# Digital_Input_LED_Monitor.net
KiCad netlist of a schematic drawn in Altium Designer
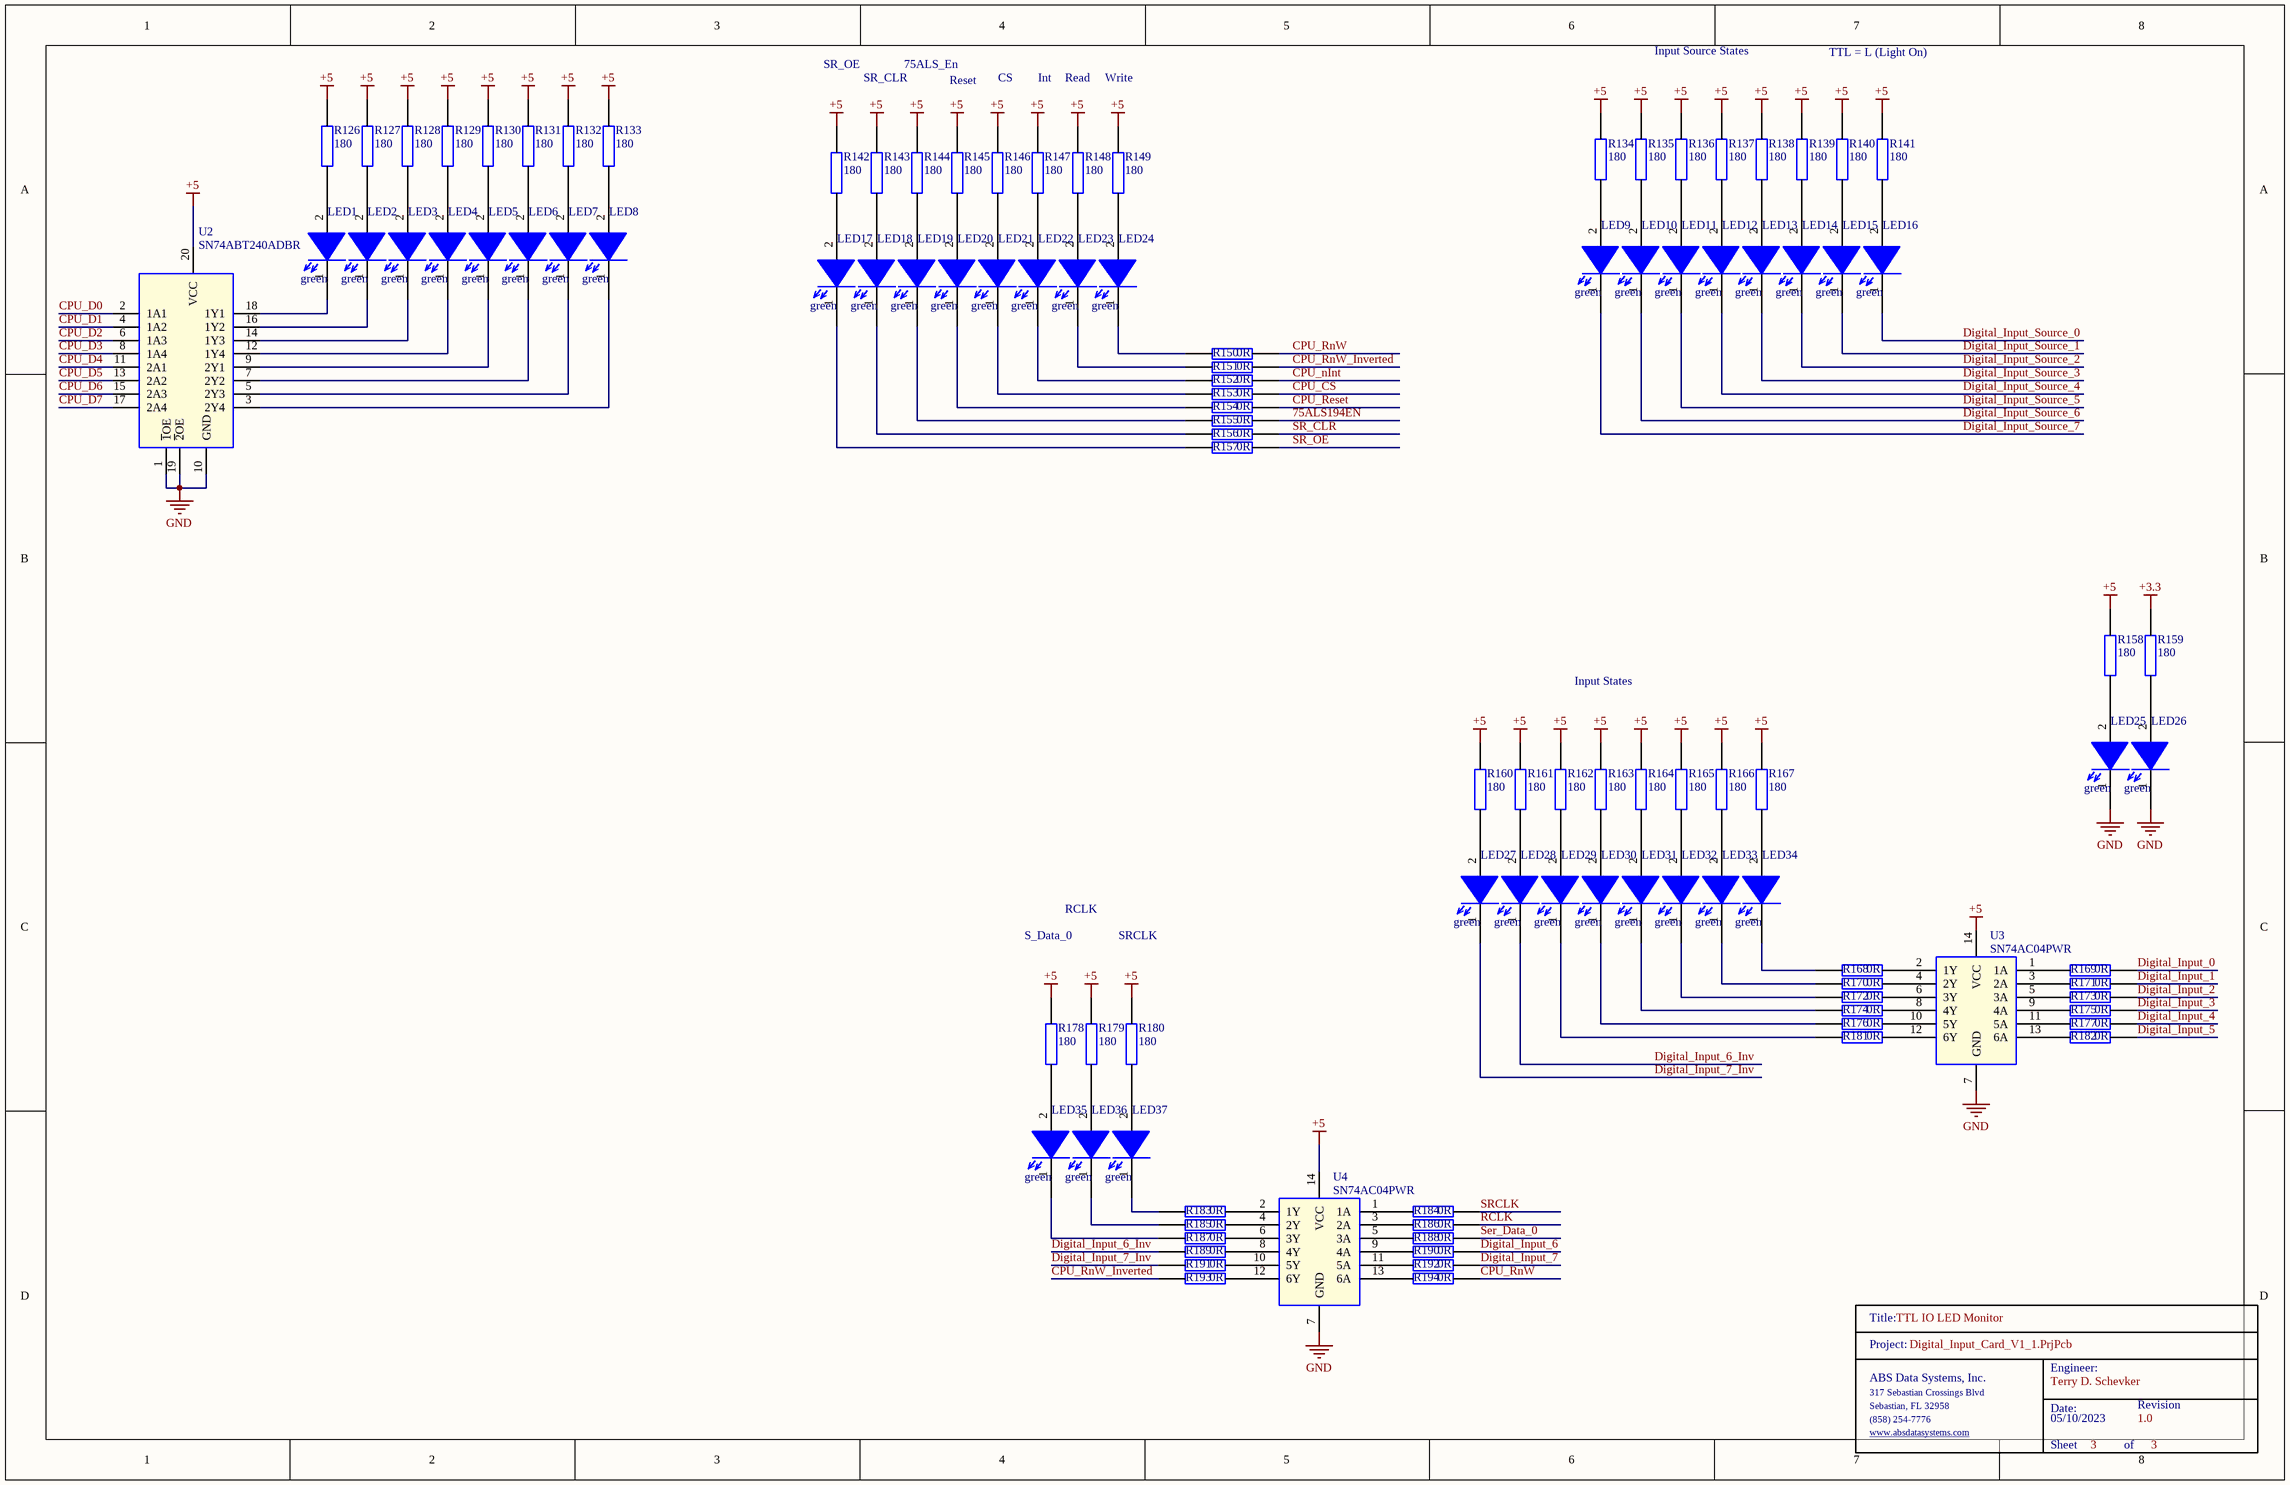
[diagram p0: Digital_Input_LED_Monitor.SchDoc]

(export (version "E")
  (design (tool "Eeschema 10.0.6"))
  (components
    (comp (ref "LED1")
      (value "green")
      (footprint "0603_Diode")
      (description "Wurth Elektronik 0603 green")
      (fields
        (field (name "MANUFACTURER") "Wurth Electronics")
        (field (name "MANUFACTURER PART NUMBER") "150060GS75000")
      )
      (libsource (lib "Misc") (part "150060GS75000"))
    )
    (comp (ref "LED2")
      (value "green")
      (footprint "0603_Diode")
      (description "Wurth Elektronik 0603 green")
      (fields
        (field (name "MANUFACTURER") "Wurth Electronics")
        (field (name "MANUFACTURER PART NUMBER") "150060GS75000")
      )
      (libsource (lib "Misc") (part "150060GS75000"))
    )
    (comp (ref "LED3")
      (value "green")
      (footprint "0603_Diode")
      (description "Wurth Elektronik 0603 green")
      (fields
        (field (name "MANUFACTURER") "Wurth Electronics")
        (field (name "MANUFACTURER PART NUMBER") "150060GS75000")
      )
      (libsource (lib "Misc") (part "150060GS75000"))
    )
    (comp (ref "LED4")
      (value "green")
      (footprint "0603_Diode")
      (description "Wurth Elektronik 0603 green")
      (fields
        (field (name "MANUFACTURER") "Wurth Electronics")
        (field (name "MANUFACTURER PART NUMBER") "150060GS75000")
      )
      (libsource (lib "Misc") (part "150060GS75000"))
    )
    (comp (ref "LED5")
      (value "green")
      (footprint "0603_Diode")
      (description "Wurth Elektronik 0603 green")
      (fields
        (field (name "MANUFACTURER") "Wurth Electronics")
        (field (name "MANUFACTURER PART NUMBER") "150060GS75000")
      )
      (libsource (lib "Misc") (part "150060GS75000"))
    )
    (comp (ref "LED6")
      (value "green")
      (footprint "0603_Diode")
      (description "Wurth Elektronik 0603 green")
      (fields
        (field (name "MANUFACTURER") "Wurth Electronics")
        (field (name "MANUFACTURER PART NUMBER") "150060GS75000")
      )
      (libsource (lib "Misc") (part "150060GS75000"))
    )
    (comp (ref "LED7")
      (value "green")
      (footprint "0603_Diode")
      (description "Wurth Elektronik 0603 green")
      (fields
        (field (name "MANUFACTURER") "Wurth Electronics")
        (field (name "MANUFACTURER PART NUMBER") "150060GS75000")
      )
      (libsource (lib "Misc") (part "150060GS75000"))
    )
    (comp (ref "LED8")
      (value "green")
      (footprint "0603_Diode")
      (description "Wurth Elektronik 0603 green")
      (fields
        (field (name "MANUFACTURER") "Wurth Electronics")
        (field (name "MANUFACTURER PART NUMBER") "150060GS75000")
      )
      (libsource (lib "Misc") (part "150060GS75000"))
    )
    (comp (ref "LED9")
      (value "green")
      (footprint "0603_Diode")
      (description "Wurth Elektronik 0603 green")
      (fields
        (field (name "MANUFACTURER") "Wurth Electronics")
        (field (name "MANUFACTURER PART NUMBER") "150060GS75000")
      )
      (libsource (lib "Misc") (part "150060GS75000"))
    )
    (comp (ref "LED10")
      (value "green")
      (footprint "0603_Diode")
      (description "Wurth Elektronik 0603 green")
      (fields
        (field (name "MANUFACTURER") "Wurth Electronics")
        (field (name "MANUFACTURER PART NUMBER") "150060GS75000")
      )
      (libsource (lib "Misc") (part "150060GS75000"))
    )
    (comp (ref "LED11")
      (value "green")
      (footprint "0603_Diode")
      (description "Wurth Elektronik 0603 green")
      (fields
        (field (name "MANUFACTURER") "Wurth Electronics")
        (field (name "MANUFACTURER PART NUMBER") "150060GS75000")
      )
      (libsource (lib "Misc") (part "150060GS75000"))
    )
    (comp (ref "LED12")
      (value "green")
      (footprint "0603_Diode")
      (description "Wurth Elektronik 0603 green")
      (fields
        (field (name "MANUFACTURER") "Wurth Electronics")
        (field (name "MANUFACTURER PART NUMBER") "150060GS75000")
      )
      (libsource (lib "Misc") (part "150060GS75000"))
    )
    (comp (ref "LED13")
      (value "green")
      (footprint "0603_Diode")
      (description "Wurth Elektronik 0603 green")
      (fields
        (field (name "MANUFACTURER") "Wurth Electronics")
        (field (name "MANUFACTURER PART NUMBER") "150060GS75000")
      )
      (libsource (lib "Misc") (part "150060GS75000"))
    )
    (comp (ref "LED14")
      (value "green")
      (footprint "0603_Diode")
      (description "Wurth Elektronik 0603 green")
      (fields
        (field (name "MANUFACTURER") "Wurth Electronics")
        (field (name "MANUFACTURER PART NUMBER") "150060GS75000")
      )
      (libsource (lib "Misc") (part "150060GS75000"))
    )
    (comp (ref "LED15")
      (value "green")
      (footprint "0603_Diode")
      (description "Wurth Elektronik 0603 green")
      (fields
        (field (name "MANUFACTURER") "Wurth Electronics")
        (field (name "MANUFACTURER PART NUMBER") "150060GS75000")
      )
      (libsource (lib "Misc") (part "150060GS75000"))
    )
    (comp (ref "LED16")
      (value "green")
      (footprint "0603_Diode")
      (description "Wurth Elektronik 0603 green")
      (fields
        (field (name "MANUFACTURER") "Wurth Electronics")
        (field (name "MANUFACTURER PART NUMBER") "150060GS75000")
      )
      (libsource (lib "Misc") (part "150060GS75000"))
    )
    (comp (ref "LED17")
      (value "green")
      (footprint "0603_Diode")
      (description "Wurth Elektronik 0603 green")
      (fields
        (field (name "MANUFACTURER") "Wurth Electronics")
        (field (name "MANUFACTURER PART NUMBER") "150060GS75000")
      )
      (libsource (lib "Misc") (part "150060GS75000"))
    )
    (comp (ref "LED18")
      (value "green")
      (footprint "0603_Diode")
      (description "Wurth Elektronik 0603 green")
      (fields
        (field (name "MANUFACTURER") "Wurth Electronics")
        (field (name "MANUFACTURER PART NUMBER") "150060GS75000")
      )
      (libsource (lib "Misc") (part "150060GS75000"))
    )
    (comp (ref "LED19")
      (value "green")
      (footprint "0603_Diode")
      (description "Wurth Elektronik 0603 green")
      (fields
        (field (name "MANUFACTURER") "Wurth Electronics")
        (field (name "MANUFACTURER PART NUMBER") "150060GS75000")
      )
      (libsource (lib "Misc") (part "150060GS75000"))
    )
    (comp (ref "LED20")
      (value "green")
      (footprint "0603_Diode")
      (description "Wurth Elektronik 0603 green")
      (fields
        (field (name "MANUFACTURER") "Wurth Electronics")
        (field (name "MANUFACTURER PART NUMBER") "150060GS75000")
      )
      (libsource (lib "Misc") (part "150060GS75000"))
    )
    (comp (ref "LED21")
      (value "green")
      (footprint "0603_Diode")
      (description "Wurth Elektronik 0603 green")
      (fields
        (field (name "MANUFACTURER") "Wurth Electronics")
        (field (name "MANUFACTURER PART NUMBER") "150060GS75000")
      )
      (libsource (lib "Misc") (part "150060GS75000"))
    )
    (comp (ref "LED22")
      (value "green")
      (footprint "0603_Diode")
      (description "Wurth Elektronik 0603 green")
      (fields
        (field (name "MANUFACTURER") "Wurth Electronics")
        (field (name "MANUFACTURER PART NUMBER") "150060GS75000")
      )
      (libsource (lib "Misc") (part "150060GS75000"))
    )
    (comp (ref "LED23")
      (value "green")
      (footprint "0603_Diode")
      (description "Wurth Elektronik 0603 green")
      (fields
        (field (name "MANUFACTURER") "Wurth Electronics")
        (field (name "MANUFACTURER PART NUMBER") "150060GS75000")
      )
      (libsource (lib "Misc") (part "150060GS75000"))
    )
    (comp (ref "LED24")
      (value "green")
      (footprint "0603_Diode")
      (description "Wurth Elektronik 0603 green")
      (fields
        (field (name "MANUFACTURER") "Wurth Electronics")
        (field (name "MANUFACTURER PART NUMBER") "150060GS75000")
      )
      (libsource (lib "Misc") (part "150060GS75000"))
    )
    (comp (ref "LED25")
      (value "green")
      (footprint "0603_Diode")
      (description "Wurth Elektronik 0603 green")
      (fields
        (field (name "MANUFACTURER") "Wurth Electronics")
        (field (name "MANUFACTURER PART NUMBER") "150060GS75000")
      )
      (libsource (lib "Misc") (part "150060GS75000"))
    )
    (comp (ref "LED26")
      (value "green")
      (footprint "0603_Diode")
      (description "Wurth Elektronik 0603 green")
      (fields
        (field (name "MANUFACTURER") "Wurth Electronics")
        (field (name "MANUFACTURER PART NUMBER") "150060GS75000")
      )
      (libsource (lib "Misc") (part "150060GS75000"))
    )
    (comp (ref "LED27")
      (value "green")
      (footprint "0603_Diode")
      (description "Wurth Elektronik 0603 green")
      (fields
        (field (name "MANUFACTURER") "Wurth Electronics")
        (field (name "MANUFACTURER PART NUMBER") "150060GS75000")
      )
      (libsource (lib "Misc") (part "150060GS75000"))
    )
    (comp (ref "LED28")
      (value "green")
      (footprint "0603_Diode")
      (description "Wurth Elektronik 0603 green")
      (fields
        (field (name "MANUFACTURER") "Wurth Electronics")
        (field (name "MANUFACTURER PART NUMBER") "150060GS75000")
      )
      (libsource (lib "Misc") (part "150060GS75000"))
    )
    (comp (ref "LED29")
      (value "green")
      (footprint "0603_Diode")
      (description "Wurth Elektronik 0603 green")
      (fields
        (field (name "MANUFACTURER") "Wurth Electronics")
        (field (name "MANUFACTURER PART NUMBER") "150060GS75000")
      )
      (libsource (lib "Misc") (part "150060GS75000"))
    )
    (comp (ref "LED30")
      (value "green")
      (footprint "0603_Diode")
      (description "Wurth Elektronik 0603 green")
      (fields
        (field (name "MANUFACTURER") "Wurth Electronics")
        (field (name "MANUFACTURER PART NUMBER") "150060GS75000")
      )
      (libsource (lib "Misc") (part "150060GS75000"))
    )
    (comp (ref "LED31")
      (value "green")
      (footprint "0603_Diode")
      (description "Wurth Elektronik 0603 green")
      (fields
        (field (name "MANUFACTURER") "Wurth Electronics")
        (field (name "MANUFACTURER PART NUMBER") "150060GS75000")
      )
      (libsource (lib "Misc") (part "150060GS75000"))
    )
    (comp (ref "LED32")
      (value "green")
      (footprint "0603_Diode")
      (description "Wurth Elektronik 0603 green")
      (fields
        (field (name "MANUFACTURER") "Wurth Electronics")
        (field (name "MANUFACTURER PART NUMBER") "150060GS75000")
      )
      (libsource (lib "Misc") (part "150060GS75000"))
    )
    (comp (ref "LED33")
      (value "green")
      (footprint "0603_Diode")
      (description "Wurth Elektronik 0603 green")
      (fields
        (field (name "MANUFACTURER") "Wurth Electronics")
        (field (name "MANUFACTURER PART NUMBER") "150060GS75000")
      )
      (libsource (lib "Misc") (part "150060GS75000"))
    )
    (comp (ref "LED34")
      (value "green")
      (footprint "0603_Diode")
      (description "Wurth Elektronik 0603 green")
      (fields
        (field (name "MANUFACTURER") "Wurth Electronics")
        (field (name "MANUFACTURER PART NUMBER") "150060GS75000")
      )
      (libsource (lib "Misc") (part "150060GS75000"))
    )
    (comp (ref "LED35")
      (value "green")
      (footprint "0603_Diode")
      (description "Wurth Elektronik 0603 green")
      (fields
        (field (name "MANUFACTURER") "Wurth Electronics")
        (field (name "MANUFACTURER PART NUMBER") "150060GS75000")
      )
      (libsource (lib "Misc") (part "150060GS75000"))
    )
    (comp (ref "LED36")
      (value "green")
      (footprint "0603_Diode")
      (description "Wurth Elektronik 0603 green")
      (fields
        (field (name "MANUFACTURER") "Wurth Electronics")
        (field (name "MANUFACTURER PART NUMBER") "150060GS75000")
      )
      (libsource (lib "Misc") (part "150060GS75000"))
    )
    (comp (ref "LED37")
      (value "green")
      (footprint "0603_Diode")
      (description "Wurth Elektronik 0603 green")
      (fields
        (field (name "MANUFACTURER") "Wurth Electronics")
        (field (name "MANUFACTURER PART NUMBER") "150060GS75000")
      )
      (libsource (lib "Misc") (part "150060GS75000"))
    )
    (comp (ref "R126")
      (value "180")
      (footprint "0603")
      (description "YAGEO 0603 180 ohm")
      (fields
        (field (name "MOUSER PART NUMBER") "603-RC0603JR-070RL")
        (field (name "MANUFACTURER_PART_NUMBER") "RC0603JR-070RL")
      )
      (libsource (lib "Resistors") (part "RC0603FR-13180RL"))
    )
    (comp (ref "R127")
      (value "180")
      (footprint "0603")
      (description "YAGEO 0603 180 ohm")
      (fields
        (field (name "MOUSER PART NUMBER") "603-RC0603JR-070RL")
        (field (name "MANUFACTURER_PART_NUMBER") "RC0603JR-070RL")
      )
      (libsource (lib "Resistors") (part "RC0603FR-13180RL"))
    )
    (comp (ref "R128")
      (value "180")
      (footprint "0603")
      (description "YAGEO 0603 180 ohm")
      (fields
        (field (name "MOUSER PART NUMBER") "603-RC0603JR-070RL")
        (field (name "MANUFACTURER_PART_NUMBER") "RC0603JR-070RL")
      )
      (libsource (lib "Resistors") (part "RC0603FR-13180RL"))
    )
    (comp (ref "R129")
      (value "180")
      (footprint "0603")
      (description "YAGEO 0603 180 ohm")
      (fields
        (field (name "MOUSER PART NUMBER") "603-RC0603JR-070RL")
        (field (name "MANUFACTURER_PART_NUMBER") "RC0603JR-070RL")
      )
      (libsource (lib "Resistors") (part "RC0603FR-13180RL"))
    )
    (comp (ref "R130")
      (value "180")
      (footprint "0603")
      (description "YAGEO 0603 180 ohm")
      (fields
        (field (name "MOUSER PART NUMBER") "603-RC0603JR-070RL")
        (field (name "MANUFACTURER_PART_NUMBER") "RC0603JR-070RL")
      )
      (libsource (lib "Resistors") (part "RC0603FR-13180RL"))
    )
    (comp (ref "R131")
      (value "180")
      (footprint "0603")
      (description "YAGEO 0603 180 ohm")
      (fields
        (field (name "MOUSER PART NUMBER") "603-RC0603JR-070RL")
        (field (name "MANUFACTURER_PART_NUMBER") "RC0603JR-070RL")
      )
      (libsource (lib "Resistors") (part "RC0603FR-13180RL"))
    )
    (comp (ref "R132")
      (value "180")
      (footprint "0603")
      (description "YAGEO 0603 180 ohm")
      (fields
        (field (name "MOUSER PART NUMBER") "603-RC0603JR-070RL")
        (field (name "MANUFACTURER_PART_NUMBER") "RC0603JR-070RL")
      )
      (libsource (lib "Resistors") (part "RC0603FR-13180RL"))
    )
    (comp (ref "R133")
      (value "180")
      (footprint "0603")
      (description "YAGEO 0603 180 ohm")
      (fields
        (field (name "MOUSER PART NUMBER") "603-RC0603JR-070RL")
        (field (name "MANUFACTURER_PART_NUMBER") "RC0603JR-070RL")
      )
      (libsource (lib "Resistors") (part "RC0603FR-13180RL"))
    )
    (comp (ref "R134")
      (value "180")
      (footprint "0603")
      (description "YAGEO 0603 180 ohm")
      (fields
        (field (name "MOUSER PART NUMBER") "603-RC0603JR-070RL")
        (field (name "MANUFACTURER_PART_NUMBER") "RC0603JR-070RL")
      )
      (libsource (lib "Resistors") (part "RC0603FR-13180RL"))
    )
    (comp (ref "R135")
      (value "180")
      (footprint "0603")
      (description "YAGEO 0603 180 ohm")
      (fields
        (field (name "MOUSER PART NUMBER") "603-RC0603JR-070RL")
        (field (name "MANUFACTURER_PART_NUMBER") "RC0603JR-070RL")
      )
      (libsource (lib "Resistors") (part "RC0603FR-13180RL"))
    )
    (comp (ref "R136")
      (value "180")
      (footprint "0603")
      (description "YAGEO 0603 180 ohm")
      (fields
        (field (name "MOUSER PART NUMBER") "603-RC0603JR-070RL")
        (field (name "MANUFACTURER_PART_NUMBER") "RC0603JR-070RL")
      )
      (libsource (lib "Resistors") (part "RC0603FR-13180RL"))
    )
    (comp (ref "R137")
      (value "180")
      (footprint "0603")
      (description "YAGEO 0603 180 ohm")
      (fields
        (field (name "MOUSER PART NUMBER") "603-RC0603JR-070RL")
        (field (name "MANUFACTURER_PART_NUMBER") "RC0603JR-070RL")
      )
      (libsource (lib "Resistors") (part "RC0603FR-13180RL"))
    )
    (comp (ref "R138")
      (value "180")
      (footprint "0603")
      (description "YAGEO 0603 180 ohm")
      (fields
        (field (name "MOUSER PART NUMBER") "603-RC0603JR-070RL")
        (field (name "MANUFACTURER_PART_NUMBER") "RC0603JR-070RL")
      )
      (libsource (lib "Resistors") (part "RC0603FR-13180RL"))
    )
    (comp (ref "R139")
      (value "180")
      (footprint "0603")
      (description "YAGEO 0603 180 ohm")
      (fields
        (field (name "MOUSER PART NUMBER") "603-RC0603JR-070RL")
        (field (name "MANUFACTURER_PART_NUMBER") "RC0603JR-070RL")
      )
      (libsource (lib "Resistors") (part "RC0603FR-13180RL"))
    )
    (comp (ref "R140")
      (value "180")
      (footprint "0603")
      (description "YAGEO 0603 180 ohm")
      (fields
        (field (name "MOUSER PART NUMBER") "603-RC0603JR-070RL")
        (field (name "MANUFACTURER_PART_NUMBER") "RC0603JR-070RL")
      )
      (libsource (lib "Resistors") (part "RC0603FR-13180RL"))
    )
    (comp (ref "R141")
      (value "180")
      (footprint "0603")
      (description "YAGEO 0603 180 ohm")
      (fields
        (field (name "MOUSER PART NUMBER") "603-RC0603JR-070RL")
        (field (name "MANUFACTURER_PART_NUMBER") "RC0603JR-070RL")
      )
      (libsource (lib "Resistors") (part "RC0603FR-13180RL"))
    )
    (comp (ref "R142")
      (value "180")
      (footprint "0603")
      (description "YAGEO 0603 180 ohm")
      (fields
        (field (name "MOUSER PART NUMBER") "603-RC0603JR-070RL")
        (field (name "MANUFACTURER_PART_NUMBER") "RC0603JR-070RL")
      )
      (libsource (lib "Resistors") (part "RC0603FR-13180RL"))
    )
    (comp (ref "R143")
      (value "180")
      (footprint "0603")
      (description "YAGEO 0603 180 ohm")
      (fields
        (field (name "MOUSER PART NUMBER") "603-RC0603JR-070RL")
        (field (name "MANUFACTURER_PART_NUMBER") "RC0603JR-070RL")
      )
      (libsource (lib "Resistors") (part "RC0603FR-13180RL"))
    )
    (comp (ref "R144")
      (value "180")
      (footprint "0603")
      (description "YAGEO 0603 180 ohm")
      (fields
        (field (name "MOUSER PART NUMBER") "603-RC0603JR-070RL")
        (field (name "MANUFACTURER_PART_NUMBER") "RC0603JR-070RL")
      )
      (libsource (lib "Resistors") (part "RC0603FR-13180RL"))
    )
    (comp (ref "R145")
      (value "180")
      (footprint "0603")
      (description "YAGEO 0603 180 ohm")
      (fields
        (field (name "MOUSER PART NUMBER") "603-RC0603JR-070RL")
        (field (name "MANUFACTURER_PART_NUMBER") "RC0603JR-070RL")
      )
      (libsource (lib "Resistors") (part "RC0603FR-13180RL"))
    )
    (comp (ref "R146")
      (value "180")
      (footprint "0603")
      (description "YAGEO 0603 180 ohm")
      (fields
        (field (name "MOUSER PART NUMBER") "603-RC0603JR-070RL")
        (field (name "MANUFACTURER_PART_NUMBER") "RC0603JR-070RL")
      )
      (libsource (lib "Resistors") (part "RC0603FR-13180RL"))
    )
    (comp (ref "R147")
      (value "180")
      (footprint "0603")
      (description "YAGEO 0603 180 ohm")
      (fields
        (field (name "MOUSER PART NUMBER") "603-RC0603JR-070RL")
        (field (name "MANUFACTURER_PART_NUMBER") "RC0603JR-070RL")
      )
      (libsource (lib "Resistors") (part "RC0603FR-13180RL"))
    )
    (comp (ref "R148")
      (value "180")
      (footprint "0603")
      (description "YAGEO 0603 180 ohm")
      (fields
        (field (name "MOUSER PART NUMBER") "603-RC0603JR-070RL")
        (field (name "MANUFACTURER_PART_NUMBER") "RC0603JR-070RL")
      )
      (libsource (lib "Resistors") (part "RC0603FR-13180RL"))
    )
    (comp (ref "R149")
      (value "180")
      (footprint "0603")
      (description "YAGEO 0603 180 ohm")
      (fields
        (field (name "MOUSER PART NUMBER") "603-RC0603JR-070RL")
        (field (name "MANUFACTURER_PART_NUMBER") "RC0603JR-070RL")
      )
      (libsource (lib "Resistors") (part "RC0603FR-13180RL"))
    )
    (comp (ref "R150")
      (value "0R")
      (footprint "0603")
      (description "YAGEO 0603 0 ohm")
      (fields
        (field (name "MOUSER PART NUMBER") "603-RC0603JR-070RL")
        (field (name "MANUFACTURER_PART_NUMBER") "RC0603JR-070RL")
      )
      (libsource (lib "Resistors") (part "RC0603JR-070RL"))
    )
    (comp (ref "R151")
      (value "0R")
      (footprint "0603")
      (description "YAGEO 0603 0 ohm")
      (fields
        (field (name "MOUSER PART NUMBER") "603-RC0603JR-070RL")
        (field (name "MANUFACTURER_PART_NUMBER") "RC0603JR-070RL")
      )
      (libsource (lib "Resistors") (part "RC0603JR-070RL"))
    )
    (comp (ref "R152")
      (value "0R")
      (footprint "0603")
      (description "YAGEO 0603 0 ohm")
      (fields
        (field (name "MOUSER PART NUMBER") "603-RC0603JR-070RL")
        (field (name "MANUFACTURER_PART_NUMBER") "RC0603JR-070RL")
      )
      (libsource (lib "Resistors") (part "RC0603JR-070RL"))
    )
    (comp (ref "R153")
      (value "0R")
      (footprint "0603")
      (description "YAGEO 0603 0 ohm")
      (fields
        (field (name "MOUSER PART NUMBER") "603-RC0603JR-070RL")
        (field (name "MANUFACTURER_PART_NUMBER") "RC0603JR-070RL")
      )
      (libsource (lib "Resistors") (part "RC0603JR-070RL"))
    )
    (comp (ref "R154")
      (value "0R")
      (footprint "0603")
      (description "YAGEO 0603 0 ohm")
      (fields
        (field (name "MOUSER PART NUMBER") "603-RC0603JR-070RL")
        (field (name "MANUFACTURER_PART_NUMBER") "RC0603JR-070RL")
      )
      (libsource (lib "Resistors") (part "RC0603JR-070RL"))
    )
    (comp (ref "R155")
      (value "0R")
      (footprint "0603")
      (description "YAGEO 0603 0 ohm")
      (fields
        (field (name "MOUSER PART NUMBER") "603-RC0603JR-070RL")
        (field (name "MANUFACTURER_PART_NUMBER") "RC0603JR-070RL")
      )
      (libsource (lib "Resistors") (part "RC0603JR-070RL"))
    )
    (comp (ref "R156")
      (value "0R")
      (footprint "0603")
      (description "YAGEO 0603 0 ohm")
      (fields
        (field (name "MOUSER PART NUMBER") "603-RC0603JR-070RL")
        (field (name "MANUFACTURER_PART_NUMBER") "RC0603JR-070RL")
      )
      (libsource (lib "Resistors") (part "RC0603JR-070RL"))
    )
    (comp (ref "R157")
      (value "0R")
      (footprint "0603")
      (description "YAGEO 0603 0 ohm")
      (fields
        (field (name "MOUSER PART NUMBER") "603-RC0603JR-070RL")
        (field (name "MANUFACTURER_PART_NUMBER") "RC0603JR-070RL")
      )
      (libsource (lib "Resistors") (part "RC0603JR-070RL"))
    )
    (comp (ref "R158")
      (value "180")
      (footprint "0603")
      (description "YAGEO 0603 180 ohm")
      (fields
        (field (name "MOUSER PART NUMBER") "603-RC0603JR-070RL")
        (field (name "MANUFACTURER_PART_NUMBER") "RC0603JR-070RL")
      )
      (libsource (lib "Resistors") (part "RC0603FR-13180RL"))
    )
    (comp (ref "R159")
      (value "180")
      (footprint "0603")
      (description "YAGEO 0603 180 ohm")
      (fields
        (field (name "MOUSER PART NUMBER") "603-RC0603JR-070RL")
        (field (name "MANUFACTURER_PART_NUMBER") "RC0603JR-070RL")
      )
      (libsource (lib "Resistors") (part "RC0603FR-13180RL"))
    )
    (comp (ref "R160")
      (value "180")
      (footprint "0603")
      (description "YAGEO 0603 180 ohm")
      (fields
        (field (name "MOUSER PART NUMBER") "603-RC0603JR-070RL")
        (field (name "MANUFACTURER_PART_NUMBER") "RC0603JR-070RL")
      )
      (libsource (lib "Resistors") (part "RC0603FR-13180RL"))
    )
    (comp (ref "R161")
      (value "180")
      (footprint "0603")
      (description "YAGEO 0603 180 ohm")
      (fields
        (field (name "MOUSER PART NUMBER") "603-RC0603JR-070RL")
        (field (name "MANUFACTURER_PART_NUMBER") "RC0603JR-070RL")
      )
      (libsource (lib "Resistors") (part "RC0603FR-13180RL"))
    )
    (comp (ref "R162")
      (value "180")
      (footprint "0603")
      (description "YAGEO 0603 180 ohm")
      (fields
        (field (name "MOUSER PART NUMBER") "603-RC0603JR-070RL")
        (field (name "MANUFACTURER_PART_NUMBER") "RC0603JR-070RL")
      )
      (libsource (lib "Resistors") (part "RC0603FR-13180RL"))
    )
    (comp (ref "R163")
      (value "180")
      (footprint "0603")
      (description "YAGEO 0603 180 ohm")
      (fields
        (field (name "MOUSER PART NUMBER") "603-RC0603JR-070RL")
        (field (name "MANUFACTURER_PART_NUMBER") "RC0603JR-070RL")
      )
      (libsource (lib "Resistors") (part "RC0603FR-13180RL"))
    )
    (comp (ref "R164")
      (value "180")
      (footprint "0603")
      (description "YAGEO 0603 180 ohm")
      (fields
        (field (name "MOUSER PART NUMBER") "603-RC0603JR-070RL")
        (field (name "MANUFACTURER_PART_NUMBER") "RC0603JR-070RL")
      )
      (libsource (lib "Resistors") (part "RC0603FR-13180RL"))
    )
    (comp (ref "R165")
      (value "180")
      (footprint "0603")
      (description "YAGEO 0603 180 ohm")
      (fields
        (field (name "MOUSER PART NUMBER") "603-RC0603JR-070RL")
        (field (name "MANUFACTURER_PART_NUMBER") "RC0603JR-070RL")
      )
      (libsource (lib "Resistors") (part "RC0603FR-13180RL"))
    )
    (comp (ref "R166")
      (value "180")
      (footprint "0603")
      (description "YAGEO 0603 180 ohm")
      (fields
        (field (name "MOUSER PART NUMBER") "603-RC0603JR-070RL")
        (field (name "MANUFACTURER_PART_NUMBER") "RC0603JR-070RL")
      )
      (libsource (lib "Resistors") (part "RC0603FR-13180RL"))
    )
    (comp (ref "R167")
      (value "180")
      (footprint "0603")
      (description "YAGEO 0603 180 ohm")
      (fields
        (field (name "MOUSER PART NUMBER") "603-RC0603JR-070RL")
        (field (name "MANUFACTURER_PART_NUMBER") "RC0603JR-070RL")
      )
      (libsource (lib "Resistors") (part "RC0603FR-13180RL"))
    )
    (comp (ref "R168")
      (value "0R")
      (footprint "0603")
      (description "YAGEO 0603 0 ohm")
      (fields
        (field (name "MOUSER PART NUMBER") "603-RC0603JR-070RL")
        (field (name "MANUFACTURER_PART_NUMBER") "RC0603JR-070RL")
      )
      (libsource (lib "Resistors") (part "RC0603JR-070RL"))
    )
    (comp (ref "R169")
      (value "0R")
      (footprint "0603")
      (description "YAGEO 0603 0 ohm")
      (fields
        (field (name "MOUSER PART NUMBER") "603-RC0603JR-070RL")
        (field (name "MANUFACTURER_PART_NUMBER") "RC0603JR-070RL")
      )
      (libsource (lib "Resistors") (part "RC0603JR-070RL"))
    )
    (comp (ref "R170")
      (value "0R")
      (footprint "0603")
      (description "YAGEO 0603 0 ohm")
      (fields
        (field (name "MOUSER PART NUMBER") "603-RC0603JR-070RL")
        (field (name "MANUFACTURER_PART_NUMBER") "RC0603JR-070RL")
      )
      (libsource (lib "Resistors") (part "RC0603JR-070RL"))
    )
    (comp (ref "R171")
      (value "0R")
      (footprint "0603")
      (description "YAGEO 0603 0 ohm")
      (fields
        (field (name "MOUSER PART NUMBER") "603-RC0603JR-070RL")
        (field (name "MANUFACTURER_PART_NUMBER") "RC0603JR-070RL")
      )
      (libsource (lib "Resistors") (part "RC0603JR-070RL"))
    )
    (comp (ref "R172")
      (value "0R")
      (footprint "0603")
      (description "YAGEO 0603 0 ohm")
      (fields
        (field (name "MOUSER PART NUMBER") "603-RC0603JR-070RL")
        (field (name "MANUFACTURER_PART_NUMBER") "RC0603JR-070RL")
      )
      (libsource (lib "Resistors") (part "RC0603JR-070RL"))
    )
    (comp (ref "R173")
      (value "0R")
      (footprint "0603")
      (description "YAGEO 0603 0 ohm")
      (fields
        (field (name "MOUSER PART NUMBER") "603-RC0603JR-070RL")
        (field (name "MANUFACTURER_PART_NUMBER") "RC0603JR-070RL")
      )
      (libsource (lib "Resistors") (part "RC0603JR-070RL"))
    )
    (comp (ref "R174")
      (value "0R")
      (footprint "0603")
      (description "YAGEO 0603 0 ohm")
      (fields
        (field (name "MOUSER PART NUMBER") "603-RC0603JR-070RL")
        (field (name "MANUFACTURER_PART_NUMBER") "RC0603JR-070RL")
      )
      (libsource (lib "Resistors") (part "RC0603JR-070RL"))
    )
    (comp (ref "R175")
      (value "0R")
      (footprint "0603")
      (description "YAGEO 0603 0 ohm")
      (fields
        (field (name "MOUSER PART NUMBER") "603-RC0603JR-070RL")
        (field (name "MANUFACTURER_PART_NUMBER") "RC0603JR-070RL")
      )
      (libsource (lib "Resistors") (part "RC0603JR-070RL"))
    )
    (comp (ref "R176")
      (value "0R")
      (footprint "0603")
      (description "YAGEO 0603 0 ohm")
      (fields
        (field (name "MOUSER PART NUMBER") "603-RC0603JR-070RL")
        (field (name "MANUFACTURER_PART_NUMBER") "RC0603JR-070RL")
      )
      (libsource (lib "Resistors") (part "RC0603JR-070RL"))
    )
    (comp (ref "R177")
      (value "0R")
      (footprint "0603")
      (description "YAGEO 0603 0 ohm")
      (fields
        (field (name "MOUSER PART NUMBER") "603-RC0603JR-070RL")
        (field (name "MANUFACTURER_PART_NUMBER") "RC0603JR-070RL")
      )
      (libsource (lib "Resistors") (part "RC0603JR-070RL"))
    )
    (comp (ref "R178")
      (value "180")
      (footprint "0603")
      (description "YAGEO 0603 180 ohm")
      (fields
        (field (name "MOUSER PART NUMBER") "603-RC0603JR-070RL")
        (field (name "MANUFACTURER_PART_NUMBER") "RC0603JR-070RL")
      )
      (libsource (lib "Resistors") (part "RC0603FR-13180RL"))
    )
    (comp (ref "R179")
      (value "180")
      (footprint "0603")
      (description "YAGEO 0603 180 ohm")
      (fields
        (field (name "MOUSER PART NUMBER") "603-RC0603JR-070RL")
        (field (name "MANUFACTURER_PART_NUMBER") "RC0603JR-070RL")
      )
      (libsource (lib "Resistors") (part "RC0603FR-13180RL"))
    )
    (comp (ref "R180")
      (value "180")
      (footprint "0603")
      (description "YAGEO 0603 180 ohm")
      (fields
        (field (name "MOUSER PART NUMBER") "603-RC0603JR-070RL")
        (field (name "MANUFACTURER_PART_NUMBER") "RC0603JR-070RL")
      )
      (libsource (lib "Resistors") (part "RC0603FR-13180RL"))
    )
    (comp (ref "R181")
      (value "0R")
      (footprint "0603")
      (description "YAGEO 0603 0 ohm")
      (fields
        (field (name "MOUSER PART NUMBER") "603-RC0603JR-070RL")
        (field (name "MANUFACTURER_PART_NUMBER") "RC0603JR-070RL")
      )
      (libsource (lib "Resistors") (part "RC0603JR-070RL"))
    )
    (comp (ref "R182")
      (value "0R")
      (footprint "0603")
      (description "YAGEO 0603 0 ohm")
      (fields
        (field (name "MOUSER PART NUMBER") "603-RC0603JR-070RL")
        (field (name "MANUFACTURER_PART_NUMBER") "RC0603JR-070RL")
      )
      (libsource (lib "Resistors") (part "RC0603JR-070RL"))
    )
    (comp (ref "R183")
      (value "0R")
      (footprint "0603")
      (description "YAGEO 0603 0 ohm")
      (fields
        (field (name "MOUSER PART NUMBER") "603-RC0603JR-070RL")
        (field (name "MANUFACTURER_PART_NUMBER") "RC0603JR-070RL")
      )
      (libsource (lib "Resistors") (part "RC0603JR-070RL"))
    )
    (comp (ref "R184")
      (value "0R")
      (footprint "0603")
      (description "YAGEO 0603 0 ohm")
      (fields
        (field (name "MOUSER PART NUMBER") "603-RC0603JR-070RL")
        (field (name "MANUFACTURER_PART_NUMBER") "RC0603JR-070RL")
      )
      (libsource (lib "Resistors") (part "RC0603JR-070RL"))
    )
    (comp (ref "R185")
      (value "0R")
      (footprint "0603")
      (description "YAGEO 0603 0 ohm")
      (fields
        (field (name "MOUSER PART NUMBER") "603-RC0603JR-070RL")
        (field (name "MANUFACTURER_PART_NUMBER") "RC0603JR-070RL")
      )
      (libsource (lib "Resistors") (part "RC0603JR-070RL"))
    )
    (comp (ref "R186")
      (value "0R")
      (footprint "0603")
      (description "YAGEO 0603 0 ohm")
      (fields
        (field (name "MOUSER PART NUMBER") "603-RC0603JR-070RL")
        (field (name "MANUFACTURER_PART_NUMBER") "RC0603JR-070RL")
      )
      (libsource (lib "Resistors") (part "RC0603JR-070RL"))
    )
    (comp (ref "R187")
      (value "0R")
      (footprint "0603")
      (description "YAGEO 0603 0 ohm")
      (fields
        (field (name "MOUSER PART NUMBER") "603-RC0603JR-070RL")
        (field (name "MANUFACTURER_PART_NUMBER") "RC0603JR-070RL")
      )
      (libsource (lib "Resistors") (part "RC0603JR-070RL"))
    )
    (comp (ref "R188")
      (value "0R")
      (footprint "0603")
      (description "YAGEO 0603 0 ohm")
      (fields
        (field (name "MOUSER PART NUMBER") "603-RC0603JR-070RL")
        (field (name "MANUFACTURER_PART_NUMBER") "RC0603JR-070RL")
      )
      (libsource (lib "Resistors") (part "RC0603JR-070RL"))
    )
    (comp (ref "R189")
      (value "0R")
      (footprint "0603")
      (description "YAGEO 0603 0 ohm")
      (fields
        (field (name "MOUSER PART NUMBER") "603-RC0603JR-070RL")
        (field (name "MANUFACTURER_PART_NUMBER") "RC0603JR-070RL")
      )
      (libsource (lib "Resistors") (part "RC0603JR-070RL"))
    )
    (comp (ref "R190")
      (value "0R")
      (footprint "0603")
      (description "YAGEO 0603 0 ohm")
      (fields
        (field (name "MOUSER PART NUMBER") "603-RC0603JR-070RL")
        (field (name "MANUFACTURER_PART_NUMBER") "RC0603JR-070RL")
      )
      (libsource (lib "Resistors") (part "RC0603JR-070RL"))
    )
    (comp (ref "R191")
      (value "0R")
      (footprint "0603")
      (description "YAGEO 0603 0 ohm")
      (fields
        (field (name "MOUSER PART NUMBER") "603-RC0603JR-070RL")
        (field (name "MANUFACTURER_PART_NUMBER") "RC0603JR-070RL")
      )
      (libsource (lib "Resistors") (part "RC0603JR-070RL"))
    )
    (comp (ref "R192")
      (value "0R")
      (footprint "0603")
      (description "YAGEO 0603 0 ohm")
      (fields
        (field (name "MOUSER PART NUMBER") "603-RC0603JR-070RL")
        (field (name "MANUFACTURER_PART_NUMBER") "RC0603JR-070RL")
      )
      (libsource (lib "Resistors") (part "RC0603JR-070RL"))
    )
    (comp (ref "R193")
      (value "0R")
      (footprint "0603")
      (description "YAGEO 0603 0 ohm")
      (fields
        (field (name "MOUSER PART NUMBER") "603-RC0603JR-070RL")
        (field (name "MANUFACTURER_PART_NUMBER") "RC0603JR-070RL")
      )
      (libsource (lib "Resistors") (part "RC0603JR-070RL"))
    )
    (comp (ref "R194")
      (value "0R")
      (footprint "0603")
      (description "YAGEO 0603 0 ohm")
      (fields
        (field (name "MOUSER PART NUMBER") "603-RC0603JR-070RL")
        (field (name "MANUFACTURER_PART_NUMBER") "RC0603JR-070RL")
      )
      (libsource (lib "Resistors") (part "RC0603JR-070RL"))
    )
    (comp (ref "TitleBlock_2") (value "TitleBlock") (libsource (lib "Misc") (part "TitleBlock")))
    (comp (ref "U2")
      (value "SN74ABT240ADBR")
      (footprint "SOP65P780X200-20N")
      (description "Octal Buffers/Drivers With 3-State Outputs")
      (fields (field (name "MOUSER PART NUMBER") "595-SN74ABT240ADBR"))
      (libsource (lib "Logic") (part "SN74ABT240ADBR"))
    )
    (comp (ref "U3")
      (value "SN74AC04PWR")
      (footprint "SOP65P640X120-14N")
      (description "Hex Inverters")
      (fields (field (name "MOUSER PART NUMBER") "595-SN74AC04PWR"))
      (libsource (lib "Logic") (part "SN74AC04PWR"))
    )
    (comp (ref "U4")
      (value "SN74AC04PWR")
      (footprint "SOP65P640X120-14N")
      (description "Hex Inverters")
      (fields (field (name "MOUSER PART NUMBER") "595-SN74AC04PWR"))
      (libsource (lib "Logic") (part "SN74AC04PWR"))
    )
  )
  (nets
    (net (code "1") (name "+3.3") (class "Default")
      (node (ref "R159") (pin "2") (pinfunction "2_2") (pintype "passive"))
    )
    (net (code "2") (name "+5") (class "Default")
      (node (ref "R126") (pin "2") (pinfunction "2_2") (pintype "passive"))
      (node (ref "R127") (pin "2") (pinfunction "2_2") (pintype "passive"))
      (node (ref "R128") (pin "2") (pinfunction "2_2") (pintype "passive"))
      (node (ref "R129") (pin "2") (pinfunction "2_2") (pintype "passive"))
      (node (ref "R130") (pin "2") (pinfunction "2_2") (pintype "passive"))
      (node (ref "R131") (pin "2") (pinfunction "2_2") (pintype "passive"))
      (node (ref "R132") (pin "2") (pinfunction "2_2") (pintype "passive"))
      (node (ref "R133") (pin "2") (pinfunction "2_2") (pintype "passive"))
      (node (ref "R134") (pin "2") (pinfunction "2_2") (pintype "passive"))
      (node (ref "R135") (pin "2") (pinfunction "2_2") (pintype "passive"))
      (node (ref "R136") (pin "2") (pinfunction "2_2") (pintype "passive"))
      (node (ref "R137") (pin "2") (pinfunction "2_2") (pintype "passive"))
      (node (ref "R138") (pin "2") (pinfunction "2_2") (pintype "passive"))
      (node (ref "R139") (pin "2") (pinfunction "2_2") (pintype "passive"))
      (node (ref "R140") (pin "2") (pinfunction "2_2") (pintype "passive"))
      (node (ref "R141") (pin "2") (pinfunction "2_2") (pintype "passive"))
      (node (ref "R142") (pin "2") (pinfunction "2_2") (pintype "passive"))
      (node (ref "R143") (pin "2") (pinfunction "2_2") (pintype "passive"))
      (node (ref "R144") (pin "2") (pinfunction "2_2") (pintype "passive"))
      (node (ref "R145") (pin "2") (pinfunction "2_2") (pintype "passive"))
      (node (ref "R146") (pin "2") (pinfunction "2_2") (pintype "passive"))
      (node (ref "R147") (pin "2") (pinfunction "2_2") (pintype "passive"))
      (node (ref "R148") (pin "2") (pinfunction "2_2") (pintype "passive"))
      (node (ref "R149") (pin "2") (pinfunction "2_2") (pintype "passive"))
      (node (ref "R158") (pin "2") (pinfunction "2_2") (pintype "passive"))
      (node (ref "R160") (pin "2") (pinfunction "2_2") (pintype "passive"))
      (node (ref "R161") (pin "2") (pinfunction "2_2") (pintype "passive"))
      (node (ref "R162") (pin "2") (pinfunction "2_2") (pintype "passive"))
      (node (ref "R163") (pin "2") (pinfunction "2_2") (pintype "passive"))
      (node (ref "R164") (pin "2") (pinfunction "2_2") (pintype "passive"))
      (node (ref "R165") (pin "2") (pinfunction "2_2") (pintype "passive"))
      (node (ref "R166") (pin "2") (pinfunction "2_2") (pintype "passive"))
      (node (ref "R167") (pin "2") (pinfunction "2_2") (pintype "passive"))
      (node (ref "R178") (pin "2") (pinfunction "2_2") (pintype "passive"))
      (node (ref "R179") (pin "2") (pinfunction "2_2") (pintype "passive"))
      (node (ref "R180") (pin "2") (pinfunction "2_2") (pintype "passive"))
      (node (ref "U2") (pin "20") (pinfunction "VCC_20") (pintype "passive"))
      (node (ref "U3") (pin "14") (pinfunction "VCC_14") (pintype "passive"))
      (node (ref "U4") (pin "14") (pinfunction "VCC_14") (pintype "passive"))
    )
    (net (code "3") (name "/75ALS194EN") (class "Default")
      (node (ref "R155") (pin "2") (pinfunction "2_2") (pintype "passive"))
    )
    (net (code "4") (name "/CPU_CS") (class "Default")
      (node (ref "R153") (pin "2") (pinfunction "2_2") (pintype "passive"))
    )
    (net (code "5") (name "/CPU_D0") (class "Default")
      (node (ref "U2") (pin "2") (pinfunction "1A1_2") (pintype "passive"))
    )
    (net (code "6") (name "/CPU_D1") (class "Default")
      (node (ref "U2") (pin "4") (pinfunction "1A2_4") (pintype "passive"))
    )
    (net (code "7") (name "/CPU_D2") (class "Default")
      (node (ref "U2") (pin "6") (pinfunction "1A3_6") (pintype "passive"))
    )
    (net (code "8") (name "/CPU_D3") (class "Default")
      (node (ref "U2") (pin "8") (pinfunction "1A4_8") (pintype "passive"))
    )
    (net (code "9") (name "/CPU_D4") (class "Default")
      (node (ref "U2") (pin "11") (pinfunction "2A1_11") (pintype "passive"))
    )
    (net (code "10") (name "/CPU_D5") (class "Default")
      (node (ref "U2") (pin "13") (pinfunction "2A2_13") (pintype "passive"))
    )
    (net (code "11") (name "/CPU_D6") (class "Default")
      (node (ref "U2") (pin "15") (pinfunction "2A3_15") (pintype "passive"))
    )
    (net (code "12") (name "/CPU_D7") (class "Default")
      (node (ref "U2") (pin "17") (pinfunction "2A4_17") (pintype "passive"))
    )
    (net (code "13") (name "/CPU_Reset") (class "Default")
      (node (ref "R154") (pin "2") (pinfunction "2_2") (pintype "passive"))
    )
    (net (code "14") (name "/CPU_RnW") (class "Default")
      (node (ref "R150") (pin "2") (pinfunction "2_2") (pintype "passive"))
      (node (ref "R194") (pin "2") (pinfunction "2_2") (pintype "passive"))
    )
    (net (code "15") (name "/CPU_RnW_Inverted") (class "Default")
      (node (ref "R151") (pin "2") (pinfunction "2_2") (pintype "passive"))
      (node (ref "R193") (pin "1") (pinfunction "1_1") (pintype "passive"))
    )
    (net (code "16") (name "/CPU_nInt") (class "Default")
      (node (ref "R152") (pin "2") (pinfunction "2_2") (pintype "passive"))
    )
    (net (code "17") (name "/Digital_Input_0") (class "Default")
      (node (ref "R169") (pin "2") (pinfunction "2_2") (pintype "passive"))
    )
    (net (code "18") (name "/Digital_Input_1") (class "Default")
      (node (ref "R171") (pin "2") (pinfunction "2_2") (pintype "passive"))
    )
    (net (code "19") (name "/Digital_Input_2") (class "Default")
      (node (ref "R173") (pin "2") (pinfunction "2_2") (pintype "passive"))
    )
    (net (code "20") (name "/Digital_Input_3") (class "Default")
      (node (ref "R175") (pin "2") (pinfunction "2_2") (pintype "passive"))
    )
    (net (code "21") (name "/Digital_Input_4") (class "Default")
      (node (ref "R177") (pin "2") (pinfunction "2_2") (pintype "passive"))
    )
    (net (code "22") (name "/Digital_Input_5") (class "Default")
      (node (ref "R182") (pin "2") (pinfunction "2_2") (pintype "passive"))
    )
    (net (code "23") (name "/Digital_Input_6") (class "Default")
      (node (ref "R190") (pin "2") (pinfunction "2_2") (pintype "passive"))
    )
    (net (code "24") (name "/Digital_Input_6_Inv") (class "Default")
      (node (ref "LED28") (pin "1") (pinfunction "K_1") (pintype "passive"))
      (node (ref "R189") (pin "1") (pinfunction "1_1") (pintype "passive"))
    )
    (net (code "25") (name "/Digital_Input_7") (class "Default")
      (node (ref "R192") (pin "2") (pinfunction "2_2") (pintype "passive"))
    )
    (net (code "26") (name "/Digital_Input_7_Inv") (class "Default")
      (node (ref "LED27") (pin "1") (pinfunction "K_1") (pintype "passive"))
      (node (ref "R191") (pin "1") (pinfunction "1_1") (pintype "passive"))
    )
    (net (code "27") (name "/Digital_Input_Source_0") (class "Default")
      (node (ref "LED16") (pin "1") (pinfunction "K_1") (pintype "passive"))
    )
    (net (code "28") (name "/Digital_Input_Source_1") (class "Default")
      (node (ref "LED15") (pin "1") (pinfunction "K_1") (pintype "passive"))
    )
    (net (code "29") (name "/Digital_Input_Source_2") (class "Default")
      (node (ref "LED14") (pin "1") (pinfunction "K_1") (pintype "passive"))
    )
    (net (code "30") (name "/Digital_Input_Source_3") (class "Default")
      (node (ref "LED13") (pin "1") (pinfunction "K_1") (pintype "passive"))
    )
    (net (code "31") (name "/Digital_Input_Source_4") (class "Default")
      (node (ref "LED12") (pin "1") (pinfunction "K_1") (pintype "passive"))
    )
    (net (code "32") (name "/Digital_Input_Source_5") (class "Default")
      (node (ref "LED11") (pin "1") (pinfunction "K_1") (pintype "passive"))
    )
    (net (code "33") (name "/Digital_Input_Source_6") (class "Default")
      (node (ref "LED10") (pin "1") (pinfunction "K_1") (pintype "passive"))
    )
    (net (code "34") (name "/Digital_Input_Source_7") (class "Default")
      (node (ref "LED9") (pin "1") (pinfunction "K_1") (pintype "passive"))
    )
    (net (code "35") (name "/RCLK") (class "Default")
      (node (ref "R186") (pin "2") (pinfunction "2_2") (pintype "passive"))
    )
    (net (code "36") (name "/SRCLK") (class "Default")
      (node (ref "R184") (pin "2") (pinfunction "2_2") (pintype "passive"))
    )
    (net (code "37") (name "/SR_CLR") (class "Default")
      (node (ref "R156") (pin "2") (pinfunction "2_2") (pintype "passive"))
    )
    (net (code "38") (name "/SR_OE") (class "Default")
      (node (ref "R157") (pin "2") (pinfunction "2_2") (pintype "passive"))
    )
    (net (code "39") (name "/Ser_Data_0") (class "Default")
      (node (ref "R188") (pin "2") (pinfunction "2_2") (pintype "passive"))
    )
    (net (code "40") (name "GND") (class "Default")
      (node (ref "LED25") (pin "1") (pinfunction "K_1") (pintype "passive"))
      (node (ref "LED26") (pin "1") (pinfunction "K_1") (pintype "passive"))
      (node (ref "U2") (pin "1") (pinfunction "~{1}OE_1") (pintype "passive"))
      (node (ref "U2") (pin "10") (pinfunction "GND_10") (pintype "passive"))
      (node (ref "U2") (pin "19") (pinfunction "~{2}OE_19") (pintype "passive"))
      (node (ref "U3") (pin "7") (pinfunction "GND_7") (pintype "passive"))
      (node (ref "U4") (pin "7") (pinfunction "GND_7") (pintype "passive"))
    )
    (net (code "41") (name "Net-(LED1-A)") (class "Default")
      (node (ref "LED1") (pin "2") (pinfunction "A_2") (pintype "passive"))
      (node (ref "R126") (pin "1") (pinfunction "1_1") (pintype "passive"))
    )
    (net (code "42") (name "Net-(LED1-K)") (class "Default")
      (node (ref "LED1") (pin "1") (pinfunction "K_1") (pintype "passive"))
      (node (ref "U2") (pin "18") (pinfunction "1Y1_18") (pintype "passive"))
    )
    (net (code "43") (name "Net-(LED2-A)") (class "Default")
      (node (ref "LED2") (pin "2") (pinfunction "A_2") (pintype "passive"))
      (node (ref "R127") (pin "1") (pinfunction "1_1") (pintype "passive"))
    )
    (net (code "44") (name "Net-(LED2-K)") (class "Default")
      (node (ref "LED2") (pin "1") (pinfunction "K_1") (pintype "passive"))
      (node (ref "U2") (pin "16") (pinfunction "1Y2_16") (pintype "passive"))
    )
    (net (code "45") (name "Net-(LED3-A)") (class "Default")
      (node (ref "LED3") (pin "2") (pinfunction "A_2") (pintype "passive"))
      (node (ref "R128") (pin "1") (pinfunction "1_1") (pintype "passive"))
    )
    (net (code "46") (name "Net-(LED3-K)") (class "Default")
      (node (ref "LED3") (pin "1") (pinfunction "K_1") (pintype "passive"))
      (node (ref "U2") (pin "14") (pinfunction "1Y3_14") (pintype "passive"))
    )
    (net (code "47") (name "Net-(LED4-A)") (class "Default")
      (node (ref "LED4") (pin "2") (pinfunction "A_2") (pintype "passive"))
      (node (ref "R129") (pin "1") (pinfunction "1_1") (pintype "passive"))
    )
    (net (code "48") (name "Net-(LED4-K)") (class "Default")
      (node (ref "LED4") (pin "1") (pinfunction "K_1") (pintype "passive"))
      (node (ref "U2") (pin "12") (pinfunction "1Y4_12") (pintype "passive"))
    )
    (net (code "49") (name "Net-(LED5-A)") (class "Default")
      (node (ref "LED5") (pin "2") (pinfunction "A_2") (pintype "passive"))
      (node (ref "R130") (pin "1") (pinfunction "1_1") (pintype "passive"))
    )
    (net (code "50") (name "Net-(LED5-K)") (class "Default")
      (node (ref "LED5") (pin "1") (pinfunction "K_1") (pintype "passive"))
      (node (ref "U2") (pin "9") (pinfunction "2Y1_9") (pintype "passive"))
    )
    (net (code "51") (name "Net-(LED6-A)") (class "Default")
      (node (ref "LED6") (pin "2") (pinfunction "A_2") (pintype "passive"))
      (node (ref "R131") (pin "1") (pinfunction "1_1") (pintype "passive"))
    )
    (net (code "52") (name "Net-(LED6-K)") (class "Default")
      (node (ref "LED6") (pin "1") (pinfunction "K_1") (pintype "passive"))
      (node (ref "U2") (pin "7") (pinfunction "2Y2_7") (pintype "passive"))
    )
    (net (code "53") (name "Net-(LED7-A)") (class "Default")
      (node (ref "LED7") (pin "2") (pinfunction "A_2") (pintype "passive"))
      (node (ref "R132") (pin "1") (pinfunction "1_1") (pintype "passive"))
    )
    (net (code "54") (name "Net-(LED7-K)") (class "Default")
      (node (ref "LED7") (pin "1") (pinfunction "K_1") (pintype "passive"))
      (node (ref "U2") (pin "5") (pinfunction "2Y3_5") (pintype "passive"))
    )
    (net (code "55") (name "Net-(LED8-A)") (class "Default")
      (node (ref "LED8") (pin "2") (pinfunction "A_2") (pintype "passive"))
      (node (ref "R133") (pin "1") (pinfunction "1_1") (pintype "passive"))
    )
    (net (code "56") (name "Net-(LED8-K)") (class "Default")
      (node (ref "LED8") (pin "1") (pinfunction "K_1") (pintype "passive"))
      (node (ref "U2") (pin "3") (pinfunction "2Y4_3") (pintype "passive"))
    )
    (net (code "57") (name "Net-(LED9-A)") (class "Default")
      (node (ref "LED9") (pin "2") (pinfunction "A_2") (pintype "passive"))
      (node (ref "R134") (pin "1") (pinfunction "1_1") (pintype "passive"))
    )
    (net (code "58") (name "Net-(LED10-A)") (class "Default")
      (node (ref "LED10") (pin "2") (pinfunction "A_2") (pintype "passive"))
      (node (ref "R135") (pin "1") (pinfunction "1_1") (pintype "passive"))
    )
    (net (code "59") (name "Net-(LED11-A)") (class "Default")
      (node (ref "LED11") (pin "2") (pinfunction "A_2") (pintype "passive"))
      (node (ref "R136") (pin "1") (pinfunction "1_1") (pintype "passive"))
    )
    (net (code "60") (name "Net-(LED12-A)") (class "Default")
      (node (ref "LED12") (pin "2") (pinfunction "A_2") (pintype "passive"))
      (node (ref "R137") (pin "1") (pinfunction "1_1") (pintype "passive"))
    )
    (net (code "61") (name "Net-(LED13-A)") (class "Default")
      (node (ref "LED13") (pin "2") (pinfunction "A_2") (pintype "passive"))
      (node (ref "R138") (pin "1") (pinfunction "1_1") (pintype "passive"))
    )
    (net (code "62") (name "Net-(LED14-A)") (class "Default")
      (node (ref "LED14") (pin "2") (pinfunction "A_2") (pintype "passive"))
      (node (ref "R139") (pin "1") (pinfunction "1_1") (pintype "passive"))
    )
    (net (code "63") (name "Net-(LED15-A)") (class "Default")
      (node (ref "LED15") (pin "2") (pinfunction "A_2") (pintype "passive"))
      (node (ref "R140") (pin "1") (pinfunction "1_1") (pintype "passive"))
    )
    (net (code "64") (name "Net-(LED16-A)") (class "Default")
      (node (ref "LED16") (pin "2") (pinfunction "A_2") (pintype "passive"))
      (node (ref "R141") (pin "1") (pinfunction "1_1") (pintype "passive"))
    )
    (net (code "65") (name "Net-(LED17-A)") (class "Default")
      (node (ref "LED17") (pin "2") (pinfunction "A_2") (pintype "passive"))
      (node (ref "R142") (pin "1") (pinfunction "1_1") (pintype "passive"))
    )
    (net (code "66") (name "Net-(LED17-K)") (class "Default")
      (node (ref "LED17") (pin "1") (pinfunction "K_1") (pintype "passive"))
      (node (ref "R157") (pin "1") (pinfunction "1_1") (pintype "passive"))
    )
    (net (code "67") (name "Net-(LED18-A)") (class "Default")
      (node (ref "LED18") (pin "2") (pinfunction "A_2") (pintype "passive"))
      (node (ref "R143") (pin "1") (pinfunction "1_1") (pintype "passive"))
    )
    (net (code "68") (name "Net-(LED18-K)") (class "Default")
      (node (ref "LED18") (pin "1") (pinfunction "K_1") (pintype "passive"))
      (node (ref "R156") (pin "1") (pinfunction "1_1") (pintype "passive"))
    )
    (net (code "69") (name "Net-(LED19-A)") (class "Default")
      (node (ref "LED19") (pin "2") (pinfunction "A_2") (pintype "passive"))
      (node (ref "R144") (pin "1") (pinfunction "1_1") (pintype "passive"))
    )
    (net (code "70") (name "Net-(LED19-K)") (class "Default")
      (node (ref "LED19") (pin "1") (pinfunction "K_1") (pintype "passive"))
      (node (ref "R155") (pin "1") (pinfunction "1_1") (pintype "passive"))
    )
    (net (code "71") (name "Net-(LED20-A)") (class "Default")
      (node (ref "LED20") (pin "2") (pinfunction "A_2") (pintype "passive"))
      (node (ref "R145") (pin "1") (pinfunction "1_1") (pintype "passive"))
    )
    (net (code "72") (name "Net-(LED20-K)") (class "Default")
      (node (ref "LED20") (pin "1") (pinfunction "K_1") (pintype "passive"))
      (node (ref "R154") (pin "1") (pinfunction "1_1") (pintype "passive"))
    )
    (net (code "73") (name "Net-(LED21-A)") (class "Default")
      (node (ref "LED21") (pin "2") (pinfunction "A_2") (pintype "passive"))
      (node (ref "R146") (pin "1") (pinfunction "1_1") (pintype "passive"))
    )
    (net (code "74") (name "Net-(LED21-K)") (class "Default")
      (node (ref "LED21") (pin "1") (pinfunction "K_1") (pintype "passive"))
      (node (ref "R153") (pin "1") (pinfunction "1_1") (pintype "passive"))
    )
    (net (code "75") (name "Net-(LED22-A)") (class "Default")
      (node (ref "LED22") (pin "2") (pinfunction "A_2") (pintype "passive"))
      (node (ref "R147") (pin "1") (pinfunction "1_1") (pintype "passive"))
    )
    (net (code "76") (name "Net-(LED22-K)") (class "Default")
      (node (ref "LED22") (pin "1") (pinfunction "K_1") (pintype "passive"))
      (node (ref "R152") (pin "1") (pinfunction "1_1") (pintype "passive"))
    )
    (net (code "77") (name "Net-(LED23-A)") (class "Default")
      (node (ref "LED23") (pin "2") (pinfunction "A_2") (pintype "passive"))
      (node (ref "R148") (pin "1") (pinfunction "1_1") (pintype "passive"))
    )
    (net (code "78") (name "Net-(LED23-K)") (class "Default")
      (node (ref "LED23") (pin "1") (pinfunction "K_1") (pintype "passive"))
      (node (ref "R151") (pin "1") (pinfunction "1_1") (pintype "passive"))
    )
    (net (code "79") (name "Net-(LED24-A)") (class "Default")
      (node (ref "LED24") (pin "2") (pinfunction "A_2") (pintype "passive"))
      (node (ref "R149") (pin "1") (pinfunction "1_1") (pintype "passive"))
    )
    (net (code "80") (name "Net-(LED24-K)") (class "Default")
      (node (ref "LED24") (pin "1") (pinfunction "K_1") (pintype "passive"))
      (node (ref "R150") (pin "1") (pinfunction "1_1") (pintype "passive"))
    )
    (net (code "81") (name "Net-(LED25-A)") (class "Default")
      (node (ref "LED25") (pin "2") (pinfunction "A_2") (pintype "passive"))
      (node (ref "R158") (pin "1") (pinfunction "1_1") (pintype "passive"))
    )
    (net (code "82") (name "Net-(LED26-A)") (class "Default")
      (node (ref "LED26") (pin "2") (pinfunction "A_2") (pintype "passive"))
      (node (ref "R159") (pin "1") (pinfunction "1_1") (pintype "passive"))
    )
    (net (code "83") (name "Net-(LED27-A)") (class "Default")
      (node (ref "LED27") (pin "2") (pinfunction "A_2") (pintype "passive"))
      (node (ref "R160") (pin "1") (pinfunction "1_1") (pintype "passive"))
    )
    (net (code "84") (name "Net-(LED28-A)") (class "Default")
      (node (ref "LED28") (pin "2") (pinfunction "A_2") (pintype "passive"))
      (node (ref "R161") (pin "1") (pinfunction "1_1") (pintype "passive"))
    )
    (net (code "85") (name "Net-(LED29-A)") (class "Default")
      (node (ref "LED29") (pin "2") (pinfunction "A_2") (pintype "passive"))
      (node (ref "R162") (pin "1") (pinfunction "1_1") (pintype "passive"))
    )
    (net (code "86") (name "Net-(LED29-K)") (class "Default")
      (node (ref "LED29") (pin "1") (pinfunction "K_1") (pintype "passive"))
      (node (ref "R181") (pin "1") (pinfunction "1_1") (pintype "passive"))
    )
    (net (code "87") (name "Net-(LED30-A)") (class "Default")
      (node (ref "LED30") (pin "2") (pinfunction "A_2") (pintype "passive"))
      (node (ref "R163") (pin "1") (pinfunction "1_1") (pintype "passive"))
    )
    (net (code "88") (name "Net-(LED30-K)") (class "Default")
      (node (ref "LED30") (pin "1") (pinfunction "K_1") (pintype "passive"))
      (node (ref "R176") (pin "1") (pinfunction "1_1") (pintype "passive"))
    )
    (net (code "89") (name "Net-(LED31-A)") (class "Default")
      (node (ref "LED31") (pin "2") (pinfunction "A_2") (pintype "passive"))
      (node (ref "R164") (pin "1") (pinfunction "1_1") (pintype "passive"))
    )
    (net (code "90") (name "Net-(LED31-K)") (class "Default")
      (node (ref "LED31") (pin "1") (pinfunction "K_1") (pintype "passive"))
      (node (ref "R174") (pin "1") (pinfunction "1_1") (pintype "passive"))
    )
    (net (code "91") (name "Net-(LED32-A)") (class "Default")
      (node (ref "LED32") (pin "2") (pinfunction "A_2") (pintype "passive"))
      (node (ref "R165") (pin "1") (pinfunction "1_1") (pintype "passive"))
    )
    (net (code "92") (name "Net-(LED32-K)") (class "Default")
      (node (ref "LED32") (pin "1") (pinfunction "K_1") (pintype "passive"))
      (node (ref "R172") (pin "1") (pinfunction "1_1") (pintype "passive"))
    )
    (net (code "93") (name "Net-(LED33-A)") (class "Default")
      (node (ref "LED33") (pin "2") (pinfunction "A_2") (pintype "passive"))
      (node (ref "R166") (pin "1") (pinfunction "1_1") (pintype "passive"))
    )
    (net (code "94") (name "Net-(LED33-K)") (class "Default")
      (node (ref "LED33") (pin "1") (pinfunction "K_1") (pintype "passive"))
      (node (ref "R170") (pin "1") (pinfunction "1_1") (pintype "passive"))
    )
    (net (code "95") (name "Net-(LED34-A)") (class "Default")
      (node (ref "LED34") (pin "2") (pinfunction "A_2") (pintype "passive"))
      (node (ref "R167") (pin "1") (pinfunction "1_1") (pintype "passive"))
    )
    (net (code "96") (name "Net-(LED34-K)") (class "Default")
      (node (ref "LED34") (pin "1") (pinfunction "K_1") (pintype "passive"))
      (node (ref "R168") (pin "1") (pinfunction "1_1") (pintype "passive"))
    )
    (net (code "97") (name "Net-(LED35-A)") (class "Default")
      (node (ref "LED35") (pin "2") (pinfunction "A_2") (pintype "passive"))
      (node (ref "R178") (pin "1") (pinfunction "1_1") (pintype "passive"))
    )
    (net (code "98") (name "Net-(LED35-K)") (class "Default")
      (node (ref "LED35") (pin "1") (pinfunction "K_1") (pintype "passive"))
      (node (ref "R187") (pin "1") (pinfunction "1_1") (pintype "passive"))
    )
    (net (code "99") (name "Net-(LED36-A)") (class "Default")
      (node (ref "LED36") (pin "2") (pinfunction "A_2") (pintype "passive"))
      (node (ref "R179") (pin "1") (pinfunction "1_1") (pintype "passive"))
    )
    (net (code "100") (name "Net-(LED36-K)") (class "Default")
      (node (ref "LED36") (pin "1") (pinfunction "K_1") (pintype "passive"))
      (node (ref "R185") (pin "1") (pinfunction "1_1") (pintype "passive"))
    )
    (net (code "101") (name "Net-(LED37-A)") (class "Default")
      (node (ref "LED37") (pin "2") (pinfunction "A_2") (pintype "passive"))
      (node (ref "R180") (pin "1") (pinfunction "1_1") (pintype "passive"))
    )
    (net (code "102") (name "Net-(LED37-K)") (class "Default")
      (node (ref "LED37") (pin "1") (pinfunction "K_1") (pintype "passive"))
      (node (ref "R183") (pin "1") (pinfunction "1_1") (pintype "passive"))
    )
    (net (code "103") (name "Net-(U3-1A)") (class "Default")
      (node (ref "R169") (pin "1") (pinfunction "1_1") (pintype "passive"))
      (node (ref "U3") (pin "1") (pinfunction "1A_1") (pintype "passive"))
    )
    (net (code "104") (name "Net-(U3-1Y)") (class "Default")
      (node (ref "R168") (pin "2") (pinfunction "2_2") (pintype "passive"))
      (node (ref "U3") (pin "2") (pinfunction "1Y_2") (pintype "passive"))
    )
    (net (code "105") (name "Net-(U3-2A)") (class "Default")
      (node (ref "R171") (pin "1") (pinfunction "1_1") (pintype "passive"))
      (node (ref "U3") (pin "3") (pinfunction "2A_3") (pintype "passive"))
    )
    (net (code "106") (name "Net-(U3-2Y)") (class "Default")
      (node (ref "R170") (pin "2") (pinfunction "2_2") (pintype "passive"))
      (node (ref "U3") (pin "4") (pinfunction "2Y_4") (pintype "passive"))
    )
    (net (code "107") (name "Net-(U3-3A)") (class "Default")
      (node (ref "R173") (pin "1") (pinfunction "1_1") (pintype "passive"))
      (node (ref "U3") (pin "5") (pinfunction "3A_5") (pintype "passive"))
    )
    (net (code "108") (name "Net-(U3-3Y)") (class "Default")
      (node (ref "R172") (pin "2") (pinfunction "2_2") (pintype "passive"))
      (node (ref "U3") (pin "6") (pinfunction "3Y_6") (pintype "passive"))
    )
    (net (code "109") (name "Net-(U3-4A)") (class "Default")
      (node (ref "R175") (pin "1") (pinfunction "1_1") (pintype "passive"))
      (node (ref "U3") (pin "9") (pinfunction "4A_9") (pintype "passive"))
    )
    (net (code "110") (name "Net-(U3-4Y)") (class "Default")
      (node (ref "R174") (pin "2") (pinfunction "2_2") (pintype "passive"))
      (node (ref "U3") (pin "8") (pinfunction "4Y_8") (pintype "passive"))
    )
    (net (code "111") (name "Net-(U3-5A)") (class "Default")
      (node (ref "R177") (pin "1") (pinfunction "1_1") (pintype "passive"))
      (node (ref "U3") (pin "11") (pinfunction "5A_11") (pintype "passive"))
    )
    (net (code "112") (name "Net-(U3-5Y)") (class "Default")
      (node (ref "R176") (pin "2") (pinfunction "2_2") (pintype "passive"))
      (node (ref "U3") (pin "10") (pinfunction "5Y_10") (pintype "passive"))
    )
    (net (code "113") (name "Net-(U3-6A)") (class "Default")
      (node (ref "R182") (pin "1") (pinfunction "1_1") (pintype "passive"))
      (node (ref "U3") (pin "13") (pinfunction "6A_13") (pintype "passive"))
    )
    (net (code "114") (name "Net-(U3-6Y)") (class "Default")
      (node (ref "R181") (pin "2") (pinfunction "2_2") (pintype "passive"))
      (node (ref "U3") (pin "12") (pinfunction "6Y_12") (pintype "passive"))
    )
    (net (code "115") (name "Net-(U4-1A)") (class "Default")
      (node (ref "R184") (pin "1") (pinfunction "1_1") (pintype "passive"))
      (node (ref "U4") (pin "1") (pinfunction "1A_1") (pintype "passive"))
    )
    (net (code "116") (name "Net-(U4-1Y)") (class "Default")
      (node (ref "R183") (pin "2") (pinfunction "2_2") (pintype "passive"))
      (node (ref "U4") (pin "2") (pinfunction "1Y_2") (pintype "passive"))
    )
    (net (code "117") (name "Net-(U4-2A)") (class "Default")
      (node (ref "R186") (pin "1") (pinfunction "1_1") (pintype "passive"))
      (node (ref "U4") (pin "3") (pinfunction "2A_3") (pintype "passive"))
    )
    (net (code "118") (name "Net-(U4-2Y)") (class "Default")
      (node (ref "R185") (pin "2") (pinfunction "2_2") (pintype "passive"))
      (node (ref "U4") (pin "4") (pinfunction "2Y_4") (pintype "passive"))
    )
    (net (code "119") (name "Net-(U4-3A)") (class "Default")
      (node (ref "R188") (pin "1") (pinfunction "1_1") (pintype "passive"))
      (node (ref "U4") (pin "5") (pinfunction "3A_5") (pintype "passive"))
    )
    (net (code "120") (name "Net-(U4-3Y)") (class "Default")
      (node (ref "R187") (pin "2") (pinfunction "2_2") (pintype "passive"))
      (node (ref "U4") (pin "6") (pinfunction "3Y_6") (pintype "passive"))
    )
    (net (code "121") (name "Net-(U4-4A)") (class "Default")
      (node (ref "R190") (pin "1") (pinfunction "1_1") (pintype "passive"))
      (node (ref "U4") (pin "9") (pinfunction "4A_9") (pintype "passive"))
    )
    (net (code "122") (name "Net-(U4-4Y)") (class "Default")
      (node (ref "R189") (pin "2") (pinfunction "2_2") (pintype "passive"))
      (node (ref "U4") (pin "8") (pinfunction "4Y_8") (pintype "passive"))
    )
    (net (code "123") (name "Net-(U4-5A)") (class "Default")
      (node (ref "R192") (pin "1") (pinfunction "1_1") (pintype "passive"))
      (node (ref "U4") (pin "11") (pinfunction "5A_11") (pintype "passive"))
    )
    (net (code "124") (name "Net-(U4-5Y)") (class "Default")
      (node (ref "R191") (pin "2") (pinfunction "2_2") (pintype "passive"))
      (node (ref "U4") (pin "10") (pinfunction "5Y_10") (pintype "passive"))
    )
    (net (code "125") (name "Net-(U4-6A)") (class "Default")
      (node (ref "R194") (pin "1") (pinfunction "1_1") (pintype "passive"))
      (node (ref "U4") (pin "13") (pinfunction "6A_13") (pintype "passive"))
    )
    (net (code "126") (name "Net-(U4-6Y)") (class "Default")
      (node (ref "R193") (pin "2") (pinfunction "2_2") (pintype "passive"))
      (node (ref "U4") (pin "12") (pinfunction "6Y_12") (pintype "passive"))
    )
  )
)
